# STM32P100.net
KiCad netlist of a schematic drawn in Altium Designer
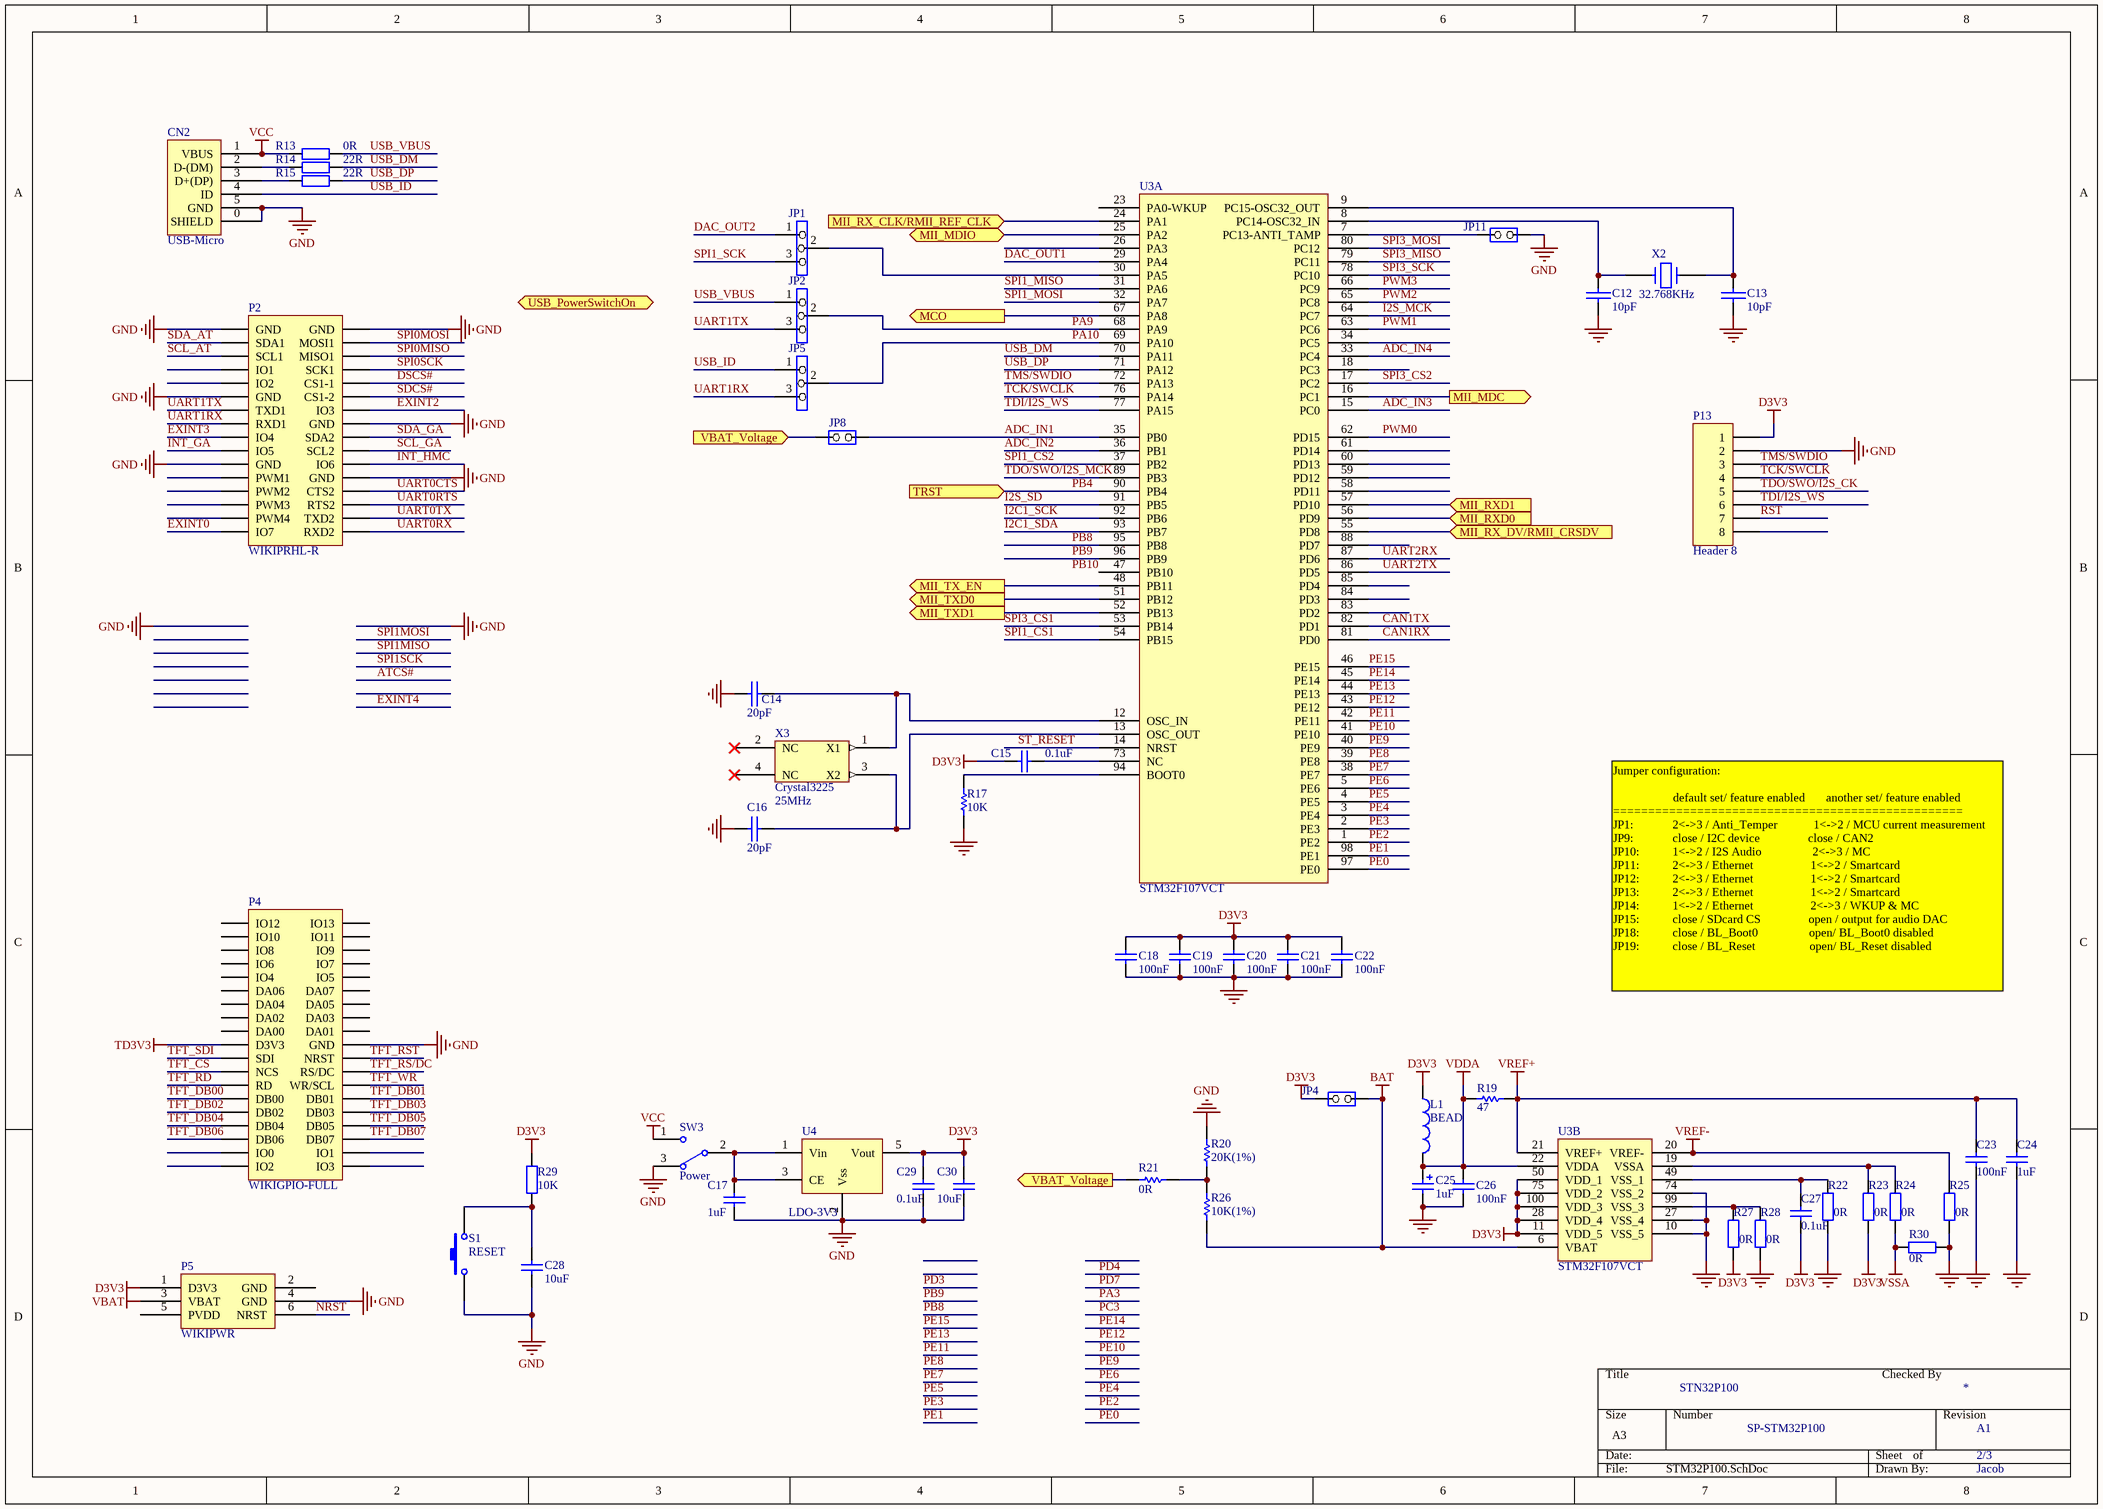
[diagram p0: STM32P100.SchDoc]

(export (version "E")
  (design (tool "Eeschema 10.0.6"))
  (components
    (comp (ref "C12")
      (value "10pF")
      (footprint "0603M")
      (description "Capacitor")
      (libsource (lib "") (part "CAP_1"))
    )
    (comp (ref "C13")
      (value "10pF")
      (footprint "0603M")
      (description "Capacitor")
      (libsource (lib "") (part "CAP_1"))
    )
    (comp (ref "C14")
      (value "20pF")
      (footprint "0603M")
      (description "Capacitor")
      (libsource (lib "*") (part "CAP"))
    )
    (comp (ref "C15")
      (value "0.1uF")
      (footprint "0603M")
      (description "Capacitor")
      (libsource (lib "Studio") (part "Cap"))
    )
    (comp (ref "C16")
      (value "20pF")
      (footprint "0603M")
      (description "Capacitor")
      (libsource (lib "*") (part "CAP"))
    )
    (comp (ref "C17")
      (value "1uF")
      (footprint "0805M")
      (description "Capacitor")
      (fields (field (name "PUBLISHER") "Altium Limited"))
      (libsource (lib "Min's Lib") (part "Cap"))
    )
    (comp (ref "C18")
      (value "100nF")
      (footprint "0603M")
      (description "Capacitor")
      (fields (field (name "PUBLISHER") "Altium Limited"))
      (libsource (lib "Miscellaneous Devices") (part "Cap"))
    )
    (comp (ref "C19")
      (value "100nF")
      (footprint "0603M")
      (description "Capacitor")
      (fields (field (name "PUBLISHER") "Altium Limited"))
      (libsource (lib "Miscellaneous Devices") (part "Cap"))
    )
    (comp (ref "C20")
      (value "100nF")
      (footprint "0603M")
      (description "Capacitor")
      (fields (field (name "PUBLISHER") "Altium Limited"))
      (libsource (lib "Miscellaneous Devices") (part "Cap"))
    )
    (comp (ref "C21")
      (value "100nF")
      (footprint "0603M")
      (description "Capacitor")
      (fields (field (name "PUBLISHER") "Altium Limited"))
      (libsource (lib "Miscellaneous Devices") (part "Cap"))
    )
    (comp (ref "C22")
      (value "100nF")
      (footprint "0603M")
      (description "Capacitor")
      (fields (field (name "PUBLISHER") "Altium Limited"))
      (libsource (lib "Miscellaneous Devices") (part "Cap"))
    )
    (comp (ref "C23")
      (value "100nF")
      (footprint "0603M")
      (description "Capacitor")
      (fields (field (name "PUBLISHER") "Altium Limited"))
      (libsource (lib "Miscellaneous Devices") (part "Cap"))
    )
    (comp (ref "C24")
      (value "1uF")
      (footprint "0603M")
      (description "Capacitor")
      (fields (field (name "PUBLISHER") "Altium Limited"))
      (libsource (lib "Miscellaneous Devices") (part "Cap"))
    )
    (comp (ref "C25")
      (value "1uF")
      (footprint "TAN-A")
      (description "Polarized Capacitor (Radial)")
      (fields (field (name "PUBLISHER") "Altium Limited"))
      (libsource (lib "Miscellaneous Devices") (part "Cap Pol1"))
    )
    (comp (ref "C26")
      (value "100nF")
      (footprint "0603M")
      (description "Capacitor")
      (fields (field (name "PUBLISHER") "Altium Limited"))
      (libsource (lib "Miscellaneous Devices") (part "Cap"))
    )
    (comp (ref "C27")
      (value "0.1uF")
      (footprint "0603M")
      (description "Capacitor")
      (libsource (lib "Studio") (part "Cap"))
    )
    (comp (ref "C28")
      (value "10uF")
      (footprint "0603L")
      (description "Capacitor")
      (fields (field (name "PUBLISHER") "Altium Limited"))
      (libsource (lib "Miscellaneous Devices") (part "Cap"))
    )
    (comp (ref "C29")
      (value "0.1uF")
      (footprint "0603M")
      (description "Capacitor")
      (fields (field (name "PUBLISHER") "Altium Limited"))
      (libsource (lib "Min's Lib") (part "Cap"))
    )
    (comp (ref "C30")
      (value "10uF")
      (footprint "0805M")
      (description "Capacitor")
      (fields (field (name "PUBLISHER") "Altium Limited"))
      (libsource (lib "Min's Lib") (part "Cap"))
    )
    (comp (ref "CN2")
      (value "USB-Micro")
      (footprint "USB-MICRO-Female")
      (libsource (lib "Connector") (part "USB-Micro"))
    )
    (comp (ref "JP1")
      (value "~")
      (footprint "HDR1X3/2.00MM")
      (libsource (lib "STR910_SCHLIB") (part "Jumper3"))
    )
    (comp (ref "JP2")
      (value "~")
      (footprint "HDR1X3/2.00MM")
      (libsource (lib "STR910_SCHLIB") (part "Jumper3"))
    )
    (comp (ref "JP4") (value "~") (footprint "HDR1X2/2.00MM") (libsource (lib "*") (part "JP2")))
    (comp (ref "JP5")
      (value "~")
      (footprint "HDR1X3/2.00MM")
      (libsource (lib "STR910_SCHLIB") (part "Jumper3"))
    )
    (comp (ref "JP8") (value "~") (footprint "HDR1X2/2.00MM") (libsource (lib "*") (part "JP2")))
    (comp (ref "JP11") (value "~") (footprint "HDR1X2/2.00MM") (libsource (lib "*") (part "JP2")))
    (comp (ref "L1")
      (value "BEAD")
      (footprint "0603L")
      (description "Inductor")
      (fields (field (name "PUBLISHER") "Altium Limited"))
      (libsource (lib "Miscellaneous Devices") (part "Inductor"))
    )
    (comp (ref "P2")
      (value "WIKIPRHL-R")
      (footprint "WIKIPRHL-R")
      (description "Header, 16-Pin, Dual row")
      (fields (field (name "PUBLISHER") "Altium Limited"))
      (libsource (lib "Connector") (part "WIKIPRHL-R"))
    )
    (comp (ref "P4")
      (value "WIKIGPIO-FULL")
      (footprint "WIKIGPIO-FULL")
      (description "Header, 19-Pin, Dual row")
      (fields (field (name "PUBLISHER") "Altium Limited"))
      (libsource (lib "Connector") (part "WIKIGPIO-FULL"))
    )
    (comp (ref "P5")
      (value "WIKIPWR")
      (footprint "WIKIPWR")
      (description "PWR HDR")
      (libsource (lib "Connector") (part "WIKIPWR"))
    )
    (comp (ref "P13")
      (value "Header 8")
      (footprint "HDR1X8/2.54MM")
      (description "Header, 8-Pin")
      (fields (field (name "PUBLISHER") "Altium Limited"))
      (libsource (lib "Miscellaneous Connectors") (part "Header 8"))
    )
    (comp (ref "R13")
      (value "0R")
      (footprint "0603M")
      (description "Resistor")
      (fields (field (name "PUBLISHER") "Altium Limited"))
      (libsource (lib "Miscellaneous Devices") (part "Res2"))
    )
    (comp (ref "R14")
      (value "22R")
      (footprint "0603M")
      (description "Resistor")
      (fields (field (name "PUBLISHER") "Altium Limited"))
      (libsource (lib "Miscellaneous Devices") (part "Res2"))
    )
    (comp (ref "R15")
      (value "22R")
      (footprint "0603M")
      (description "Resistor")
      (fields (field (name "PUBLISHER") "Altium Limited"))
      (libsource (lib "Miscellaneous Devices") (part "Res2"))
    )
    (comp (ref "R17")
      (value "10K")
      (footprint "0603M")
      (description "Resistor")
      (fields (field (name "PUBLISHER") "Altium Limited"))
      (libsource (lib "Miscellaneous Devices") (part "res1"))
    )
    (comp (ref "R19")
      (value "47")
      (footprint "0603M")
      (description "Resistor")
      (fields (field (name "PUBLISHER") "Altium Limited"))
      (libsource (lib "Miscellaneous Devices") (part "Res1"))
    )
    (comp (ref "R20")
      (value "20K(1%)")
      (footprint "0603M")
      (description "Resistor")
      (fields (field (name "PUBLISHER") "Altium Limited"))
      (libsource (lib "Miscellaneous Devices") (part "res1"))
    )
    (comp (ref "R21")
      (value "0R")
      (footprint "0603M")
      (description "Resistor")
      (fields (field (name "PUBLISHER") "Altium Limited"))
      (libsource (lib "Miscellaneous Devices") (part "res1"))
    )
    (comp (ref "R22")
      (value "0R")
      (footprint "0603M")
      (description "Resistor")
      (fields (field (name "PUBLISHER") "Altium Limited"))
      (libsource (lib "") (part "Res2_1"))
    )
    (comp (ref "R23")
      (value "0R")
      (footprint "0603M")
      (description "Resistor")
      (fields (field (name "PUBLISHER") "Altium Limited"))
      (libsource (lib "") (part "Res2_1"))
    )
    (comp (ref "R24")
      (value "0R")
      (footprint "0603M")
      (description "Resistor")
      (fields (field (name "PUBLISHER") "Altium Limited"))
      (libsource (lib "") (part "Res2_1"))
    )
    (comp (ref "R25")
      (value "0R")
      (footprint "0603M")
      (description "Resistor")
      (fields (field (name "PUBLISHER") "Altium Limited"))
      (libsource (lib "") (part "Res2_1"))
    )
    (comp (ref "R26")
      (value "10K(1%)")
      (footprint "0603M")
      (description "Resistor")
      (fields (field (name "PUBLISHER") "Altium Limited"))
      (libsource (lib "Miscellaneous Devices") (part "res1"))
    )
    (comp (ref "R27")
      (value "0R")
      (footprint "0603M")
      (description "Resistor")
      (fields (field (name "PUBLISHER") "Altium Limited"))
      (libsource (lib "") (part "Res2_1"))
    )
    (comp (ref "R28")
      (value "0R")
      (footprint "0603M")
      (description "Resistor")
      (fields (field (name "PUBLISHER") "Altium Limited"))
      (libsource (lib "") (part "Res2_1"))
    )
    (comp (ref "R29")
      (value "10K")
      (footprint "0603L")
      (description "Resistor")
      (fields (field (name "PUBLISHER") "Altium Limited"))
      (libsource (lib "") (part "Res2_2"))
    )
    (comp (ref "R30")
      (value "0R")
      (footprint "0603M")
      (description "Resistor")
      (fields (field (name "PUBLISHER") "Altium Limited"))
      (libsource (lib "") (part "Res2_3"))
    )
    (comp (ref "S1")
      (value "RESET")
      (footprint "KEY 6.1*4.0mm")
      (description "Switch")
      (fields (field (name "PUBLISHER") "Altium Limited"))
      (libsource (lib "Miscellaneous Devices") (part "SW-PB"))
    )
    (comp (ref "SW3")
      (value "Power")
      (footprint "HDR1X3/2.54MM")
      (description "SPDT Subminiature Toggle Switch, Right Angle Mounting, Vertical Actuation")
      (fields (field (name "PUBLISHER") "Altium Limited"))
      (libsource (lib "Miscellaneous Devices") (part "SW-SPDT"))
    )
    (comp (ref "U3")
      (value "STM32F107VCT")
      (footprint "LQFP100_N")
      (libsource (lib "MB784") (part "BARRACUDA_256K"))
    )
    (comp (ref "U4")
      (value "LDO-3V3")
      (footprint "SOT23-5")
      (description "LDO")
      (libsource (lib "Min's Lib") (part "XC6219"))
    )
    (comp (ref "X2")
      (value "32.768KHz")
      (footprint "XTAL_32")
      (description "Crystal")
      (libsource (lib "*") (part "CRYSTAL"))
    )
    (comp (ref "X3")
      (value "Crystal3225")
      (footprint "osc3225")
      (fields (field (name "ALTIUM_VALUE") "25MHz"))
      (libsource (lib "Studio") (part "Crystal322"))
    )
  )
  (nets
    (net (code "1") (name "/ADC_IN1") (class "Default")
      (node (ref "JP8") (pin "1") (pinfunction "COMMON_1") (pintype "passive"))
      (node (ref "U3") (pin "35") (pinfunction "PB0_35") (pintype "passive"))
    )
    (net (code "2") (name "/ADC_IN2") (class "Default")
      (node (ref "U3") (pin "36") (pinfunction "PB1_36") (pintype "passive"))
    )
    (net (code "3") (name "/ADC_IN3") (class "Default")
      (node (ref "U3") (pin "15") (pinfunction "PC0_15") (pintype "passive"))
    )
    (net (code "4") (name "/ADC_IN4") (class "Default")
      (node (ref "U3") (pin "33") (pinfunction "PC4_33") (pintype "passive"))
    )
    (net (code "6") (name "/CAN1RX") (class "Default")
      (node (ref "U3") (pin "81") (pinfunction "PD0_81") (pintype "passive"))
    )
    (net (code "7") (name "/CAN1TX") (class "Default")
      (node (ref "U3") (pin "82") (pinfunction "PD1_82") (pintype "passive"))
    )
    (net (code "8") (name "/DAC_OUT1") (class "Default")
      (node (ref "U3") (pin "29") (pinfunction "PA4_29") (pintype "passive"))
    )
    (net (code "9") (name "/DAC_OUT2") (class "Default") (node (ref "JP1") (pin "1") (pintype "passive")))
    (net (code "10") (name "/DSCS#") (class "Default")
      (node (ref "P2") (pin "10") (pinfunction "CS1-1_10") (pintype "passive"))
    )
    (net (code "11") (name "/EXINT0") (class "Default")
      (node (ref "P2") (pin "31") (pinfunction "IO7_31") (pintype "passive"))
    )
    (net (code "12") (name "/EXINT2") (class "Default")
      (node (ref "P2") (pin "14") (pinfunction "IO3_14") (pintype "passive"))
    )
    (net (code "13") (name "/EXINT3") (class "Default")
      (node (ref "P2") (pin "17") (pinfunction "IO4_17") (pintype "passive"))
    )
    (net (code "15") (name "/I2C1_SCK") (class "Default")
      (node (ref "U3") (pin "92") (pinfunction "PB6_92") (pintype "passive"))
    )
    (net (code "16") (name "/I2C1_SDA") (class "Default")
      (node (ref "U3") (pin "93") (pinfunction "PB7_93") (pintype "passive"))
    )
    (net (code "17") (name "/I2S_MCK") (class "Default")
      (node (ref "U3") (pin "64") (pinfunction "PC7_64") (pintype "passive"))
    )
    (net (code "18") (name "/I2S_SD") (class "Default")
      (node (ref "U3") (pin "91") (pinfunction "PB5_91") (pintype "passive"))
    )
    (net (code "19") (name "/INT_GA") (class "Default")
      (node (ref "P2") (pin "19") (pinfunction "IO5_19") (pintype "passive"))
    )
    (net (code "20") (name "/INT_HMC") (class "Default")
      (node (ref "P2") (pin "22") (pinfunction "IO6_22") (pintype "passive"))
    )
    (net (code "21") (name "/MCO") (class "Default")
      (node (ref "U3") (pin "67") (pinfunction "PA8_67") (pintype "passive"))
    )
    (net (code "22") (name "/MII_MDC") (class "Default")
      (node (ref "U3") (pin "16") (pinfunction "PC1_16") (pintype "passive"))
    )
    (net (code "23") (name "/MII_MDIO") (class "Default")
      (node (ref "U3") (pin "25") (pinfunction "PA2_25") (pintype "passive"))
    )
    (net (code "24") (name "/MII_RXD0") (class "Default")
      (node (ref "U3") (pin "56") (pinfunction "PD9_56") (pintype "passive"))
    )
    (net (code "25") (name "/MII_RXD1") (class "Default")
      (node (ref "U3") (pin "57") (pinfunction "PD10_57") (pintype "passive"))
    )
    (net (code "26") (name "/MII_RX_CLK{slash}RMII_REF_CLK") (class "Default")
      (node (ref "U3") (pin "24") (pinfunction "PA1_24") (pintype "passive"))
    )
    (net (code "27") (name "/MII_RX_DV{slash}RMII_CRSDV") (class "Default")
      (node (ref "U3") (pin "55") (pinfunction "PD8_55") (pintype "passive"))
    )
    (net (code "28") (name "/MII_TXD0") (class "Default")
      (node (ref "U3") (pin "51") (pinfunction "PB12_51") (pintype "passive"))
    )
    (net (code "29") (name "/MII_TXD1") (class "Default")
      (node (ref "U3") (pin "52") (pinfunction "PB13_52") (pintype "passive"))
    )
    (net (code "30") (name "/MII_TX_EN") (class "Default")
      (node (ref "U3") (pin "48") (pinfunction "PB11_48") (pintype "passive"))
    )
    (net (code "31") (name "/NRST") (class "Default")
      (node (ref "P5") (pin "6") (pinfunction "NRST_6") (pintype "passive"))
    )
    (net (code "33") (name "/PA9") (class "Default")
      (node (ref "JP2") (pin "2") (pintype "passive"))
      (node (ref "U3") (pin "68") (pinfunction "PA9_68") (pintype "passive"))
    )
    (net (code "34") (name "/PA10") (class "Default")
      (node (ref "JP5") (pin "2") (pintype "passive"))
      (node (ref "U3") (pin "69") (pinfunction "PA10_69") (pintype "passive"))
    )
    (net (code "35") (name "/PB4") (class "Default")
      (node (ref "U3") (pin "90") (pinfunction "PB4_90") (pintype "passive"))
    )
    (net (code "36") (name "/PB8") (class "Default")
      (node (ref "U3") (pin "95") (pinfunction "PB8_95") (pintype "passive"))
    )
    (net (code "37") (name "/PB9") (class "Default")
      (node (ref "U3") (pin "96") (pinfunction "PB9_96") (pintype "passive"))
    )
    (net (code "43") (name "/PE0") (class "Default")
      (node (ref "U3") (pin "97") (pinfunction "PE0_97") (pintype "passive"))
    )
    (net (code "44") (name "/PE1") (class "Default")
      (node (ref "U3") (pin "98") (pinfunction "PE1_98") (pintype "passive"))
    )
    (net (code "45") (name "/PE2") (class "Default")
      (node (ref "U3") (pin "1") (pinfunction "PE2_1") (pintype "passive"))
    )
    (net (code "46") (name "/PE3") (class "Default")
      (node (ref "U3") (pin "2") (pinfunction "PE3_2") (pintype "passive"))
    )
    (net (code "47") (name "/PE4") (class "Default")
      (node (ref "U3") (pin "3") (pinfunction "PE4_3") (pintype "passive"))
    )
    (net (code "48") (name "/PE5") (class "Default")
      (node (ref "U3") (pin "4") (pinfunction "PE5_4") (pintype "passive"))
    )
    (net (code "49") (name "/PE6") (class "Default")
      (node (ref "U3") (pin "5") (pinfunction "PE6_5") (pintype "passive"))
    )
    (net (code "50") (name "/PE7") (class "Default")
      (node (ref "U3") (pin "38") (pinfunction "PE7_38") (pintype "passive"))
    )
    (net (code "51") (name "/PE8") (class "Default")
      (node (ref "U3") (pin "39") (pinfunction "PE8_39") (pintype "passive"))
    )
    (net (code "52") (name "/PE9") (class "Default")
      (node (ref "U3") (pin "40") (pinfunction "PE9_40") (pintype "passive"))
    )
    (net (code "53") (name "/PE10") (class "Default")
      (node (ref "U3") (pin "41") (pinfunction "PE10_41") (pintype "passive"))
    )
    (net (code "54") (name "/PE11") (class "Default")
      (node (ref "U3") (pin "42") (pinfunction "PE11_42") (pintype "passive"))
    )
    (net (code "55") (name "/PE12") (class "Default")
      (node (ref "U3") (pin "43") (pinfunction "PE12_43") (pintype "passive"))
    )
    (net (code "56") (name "/PE13") (class "Default")
      (node (ref "U3") (pin "44") (pinfunction "PE13_44") (pintype "passive"))
    )
    (net (code "57") (name "/PE14") (class "Default")
      (node (ref "U3") (pin "45") (pinfunction "PE14_45") (pintype "passive"))
    )
    (net (code "58") (name "/PE15") (class "Default")
      (node (ref "U3") (pin "46") (pinfunction "PE15_46") (pintype "passive"))
    )
    (net (code "59") (name "/PWM0") (class "Default")
      (node (ref "U3") (pin "62") (pinfunction "PD15_62") (pintype "passive"))
    )
    (net (code "60") (name "/PWM1") (class "Default")
      (node (ref "U3") (pin "63") (pinfunction "PC6_63") (pintype "passive"))
    )
    (net (code "61") (name "/PWM2") (class "Default")
      (node (ref "U3") (pin "65") (pinfunction "PC8_65") (pintype "passive"))
    )
    (net (code "62") (name "/PWM3") (class "Default")
      (node (ref "U3") (pin "66") (pinfunction "PC9_66") (pintype "passive"))
    )
    (net (code "63") (name "/RST") (class "Default")
      (node (ref "P13") (pin "7") (pinfunction "7_7") (pintype "passive"))
    )
    (net (code "64") (name "/SCL_AT") (class "Default")
      (node (ref "P2") (pin "5") (pinfunction "SCL1_5") (pintype "passive"))
    )
    (net (code "65") (name "/SCL_GA") (class "Default")
      (node (ref "P2") (pin "20") (pinfunction "SCL2_20") (pintype "passive"))
    )
    (net (code "66") (name "/SDA_AT") (class "Default")
      (node (ref "P2") (pin "3") (pinfunction "SDA1_3") (pintype "passive"))
    )
    (net (code "67") (name "/SDA_GA") (class "Default")
      (node (ref "P2") (pin "18") (pinfunction "SDA2_18") (pintype "passive"))
    )
    (net (code "68") (name "/SDCS#") (class "Default")
      (node (ref "P2") (pin "12") (pinfunction "CS1-2_12") (pintype "passive"))
    )
    (net (code "69") (name "/SPI0MISO") (class "Default")
      (node (ref "P2") (pin "6") (pinfunction "MISO1_6") (pintype "passive"))
    )
    (net (code "70") (name "/SPI0MOSI") (class "Default")
      (node (ref "P2") (pin "4") (pinfunction "MOSI1_4") (pintype "passive"))
    )
    (net (code "71") (name "/SPI0SCK") (class "Default")
      (node (ref "P2") (pin "8") (pinfunction "SCK1_8") (pintype "passive"))
    )
    (net (code "75") (name "/SPI1_CS1") (class "Default")
      (node (ref "U3") (pin "54") (pinfunction "PB15_54") (pintype "passive"))
    )
    (net (code "76") (name "/SPI1_CS2") (class "Default")
      (node (ref "U3") (pin "37") (pinfunction "PB2_37") (pintype "passive"))
    )
    (net (code "77") (name "/SPI1_MISO") (class "Default")
      (node (ref "U3") (pin "31") (pinfunction "PA6_31") (pintype "passive"))
    )
    (net (code "78") (name "/SPI1_MOSI") (class "Default")
      (node (ref "U3") (pin "32") (pinfunction "PA7_32") (pintype "passive"))
    )
    (net (code "79") (name "/SPI1_SCK") (class "Default") (node (ref "JP1") (pin "3") (pintype "passive")))
    (net (code "80") (name "/SPI3_CS1") (class "Default")
      (node (ref "U3") (pin "53") (pinfunction "PB14_53") (pintype "passive"))
    )
    (net (code "81") (name "/SPI3_CS2") (class "Default")
      (node (ref "U3") (pin "17") (pinfunction "PC2_17") (pintype "passive"))
    )
    (net (code "82") (name "/SPI3_MISO") (class "Default")
      (node (ref "U3") (pin "79") (pinfunction "PC11_79") (pintype "passive"))
    )
    (net (code "83") (name "/SPI3_MOSI") (class "Default")
      (node (ref "U3") (pin "80") (pinfunction "PC12_80") (pintype "passive"))
    )
    (net (code "84") (name "/SPI3_SCK") (class "Default")
      (node (ref "U3") (pin "78") (pinfunction "PC10_78") (pintype "passive"))
    )
    (net (code "85") (name "/ST_RESET") (class "Default")
      (node (ref "U3") (pin "14") (pinfunction "NRST_14") (pintype "passive"))
    )
    (net (code "86") (name "/TCK{slash}SWCLK") (class "Default")
      (node (ref "P13") (pin "4") (pinfunction "4_4") (pintype "passive"))
      (node (ref "U3") (pin "76") (pinfunction "PA14_76") (pintype "passive"))
    )
    (net (code "87") (name "/TDI{slash}I2S_WS") (class "Default")
      (node (ref "P13") (pin "6") (pinfunction "6_6") (pintype "passive"))
      (node (ref "U3") (pin "77") (pinfunction "PA15_77") (pintype "passive"))
    )
    (net (code "88") (name "/TDO{slash}SWO{slash}I2S_CK") (class "Default")
      (node (ref "P13") (pin "5") (pinfunction "5_5") (pintype "passive"))
    )
    (net (code "89") (name "/TDO{slash}SWO{slash}I2S_MCK") (class "Default")
      (node (ref "U3") (pin "89") (pinfunction "PB3_89") (pintype "passive"))
    )
    (net (code "90") (name "/TFT_CS") (class "Default")
      (node (ref "P4") (pin "23") (pinfunction "NCS_23") (pintype "passive"))
    )
    (net (code "91") (name "/TFT_DB00") (class "Default")
      (node (ref "P4") (pin "27") (pinfunction "DB00_27") (pintype "passive"))
    )
    (net (code "92") (name "/TFT_DB01") (class "Default")
      (node (ref "P4") (pin "28") (pinfunction "DB01_28") (pintype "passive"))
    )
    (net (code "93") (name "/TFT_DB02") (class "Default")
      (node (ref "P4") (pin "29") (pinfunction "DB02_29") (pintype "passive"))
    )
    (net (code "94") (name "/TFT_DB03") (class "Default")
      (node (ref "P4") (pin "30") (pinfunction "DB03_30") (pintype "passive"))
    )
    (net (code "95") (name "/TFT_DB04") (class "Default")
      (node (ref "P4") (pin "31") (pinfunction "DB04_31") (pintype "passive"))
    )
    (net (code "96") (name "/TFT_DB05") (class "Default")
      (node (ref "P4") (pin "32") (pinfunction "DB05_32") (pintype "passive"))
    )
    (net (code "97") (name "/TFT_DB06") (class "Default")
      (node (ref "P4") (pin "33") (pinfunction "DB06_33") (pintype "passive"))
    )
    (net (code "98") (name "/TFT_DB07") (class "Default")
      (node (ref "P4") (pin "34") (pinfunction "DB07_34") (pintype "passive"))
    )
    (net (code "99") (name "/TFT_RD") (class "Default")
      (node (ref "P4") (pin "25") (pinfunction "RD_25") (pintype "passive"))
    )
    (net (code "100") (name "/TFT_RST") (class "Default")
      (node (ref "P4") (pin "22") (pinfunction "NRST_22") (pintype "passive"))
    )
    (net (code "101") (name "/TFT_RS{slash}DC") (class "Default")
      (node (ref "P4") (pin "24") (pinfunction "RS/DC_24") (pintype "passive"))
    )
    (net (code "102") (name "/TFT_SDI") (class "Default")
      (node (ref "P4") (pin "21") (pinfunction "SDI_21") (pintype "passive"))
    )
    (net (code "103") (name "/TFT_WR") (class "Default")
      (node (ref "P4") (pin "26") (pinfunction "WR/SCL_26") (pintype "passive"))
    )
    (net (code "104") (name "/TMS{slash}SWDIO") (class "Default")
      (node (ref "P13") (pin "3") (pinfunction "3_3") (pintype "passive"))
      (node (ref "U3") (pin "72") (pinfunction "PA13_72") (pintype "passive"))
    )
    (net (code "105") (name "/UART0CTS") (class "Default")
      (node (ref "P2") (pin "26") (pinfunction "CTS2_26") (pintype "passive"))
    )
    (net (code "106") (name "/UART0RTS") (class "Default")
      (node (ref "P2") (pin "28") (pinfunction "RTS2_28") (pintype "passive"))
    )
    (net (code "107") (name "/UART0RX") (class "Default")
      (node (ref "P2") (pin "32") (pinfunction "RXD2_32") (pintype "passive"))
    )
    (net (code "108") (name "/UART0TX") (class "Default")
      (node (ref "P2") (pin "30") (pinfunction "TXD2_30") (pintype "passive"))
    )
    (net (code "109") (name "/UART1RX") (class "Default")
      (node (ref "JP5") (pin "3") (pintype "passive"))
      (node (ref "P2") (pin "15") (pinfunction "RXD1_15") (pintype "passive"))
    )
    (net (code "110") (name "/UART1TX") (class "Default")
      (node (ref "JP2") (pin "3") (pintype "passive"))
      (node (ref "P2") (pin "13") (pinfunction "TXD1_13") (pintype "passive"))
    )
    (net (code "111") (name "/UART2RX") (class "Default")
      (node (ref "U3") (pin "87") (pinfunction "PD6_87") (pintype "passive"))
    )
    (net (code "112") (name "/UART2TX") (class "Default")
      (node (ref "U3") (pin "86") (pinfunction "PD5_86") (pintype "passive"))
    )
    (net (code "113") (name "/USB_DM") (class "Default")
      (node (ref "R14") (pin "2") (pinfunction "2_2") (pintype "passive"))
      (node (ref "U3") (pin "70") (pinfunction "PA11_70") (pintype "passive"))
    )
    (net (code "114") (name "/USB_DP") (class "Default")
      (node (ref "R15") (pin "2") (pinfunction "2_2") (pintype "passive"))
      (node (ref "U3") (pin "71") (pinfunction "PA12_71") (pintype "passive"))
    )
    (net (code "115") (name "/USB_ID") (class "Default")
      (node (ref "CN2") (pin "4") (pinfunction "ID_4") (pintype "passive"))
      (node (ref "JP5") (pin "1") (pintype "passive"))
    )
    (net (code "117") (name "/USB_VBUS") (class "Default")
      (node (ref "JP2") (pin "1") (pintype "passive"))
      (node (ref "R13") (pin "2") (pinfunction "2_2") (pintype "passive"))
    )
    (net (code "118") (name "/VBAT_Voltage") (class "Default")
      (node (ref "JP8") (pin "2") (pinfunction "NO_2") (pintype "passive"))
      (node (ref "R21") (pin "1") (pinfunction "1_1") (pintype "passive"))
    )
    (net (code "119") (name "BAT") (class "Default")
      (node (ref "JP4") (pin "1") (pinfunction "COMMON_1") (pintype "passive"))
      (node (ref "R26") (pin "2") (pinfunction "2_2") (pintype "passive"))
      (node (ref "U3") (pin "6") (pinfunction "VBAT_6") (pintype "passive"))
    )
    (net (code "120") (name "D3V3") (class "Default")
      (node (ref "C15") (pin "1") (pinfunction "1_1") (pintype "passive"))
      (node (ref "C18") (pin "1") (pinfunction "1_1") (pintype "passive"))
      (node (ref "C19") (pin "1") (pinfunction "1_1") (pintype "passive"))
      (node (ref "C20") (pin "1") (pinfunction "1_1") (pintype "passive"))
      (node (ref "C21") (pin "1") (pinfunction "1_1") (pintype "passive"))
      (node (ref "C22") (pin "1") (pinfunction "1_1") (pintype "passive"))
      (node (ref "C27") (pin "1") (pinfunction "1_1") (pintype "passive"))
      (node (ref "C29") (pin "1") (pinfunction "1_1") (pintype "passive"))
      (node (ref "C30") (pin "1") (pinfunction "1_1") (pintype "passive"))
      (node (ref "JP4") (pin "2") (pinfunction "NO_2") (pintype "passive"))
      (node (ref "L1") (pin "1") (pinfunction "1_1") (pintype "passive"))
      (node (ref "P13") (pin "1") (pinfunction "1_1") (pintype "passive"))
      (node (ref "P5") (pin "1") (pinfunction "D3V3_1") (pintype "passive"))
      (node (ref "R23") (pin "2") (pinfunction "2_2") (pintype "passive"))
      (node (ref "R27") (pin "2") (pinfunction "2_2") (pintype "passive"))
      (node (ref "R29") (pin "2") (pinfunction "2_2") (pintype "passive"))
      (node (ref "U3") (pin "100") (pinfunction "VDD_3_100") (pintype "passive"))
      (node (ref "U3") (pin "11") (pinfunction "VDD_5_11") (pintype "passive"))
      (node (ref "U3") (pin "28") (pinfunction "VDD_4_28") (pintype "passive"))
      (node (ref "U3") (pin "50") (pinfunction "VDD_1_50") (pintype "passive"))
      (node (ref "U3") (pin "75") (pinfunction "VDD_2_75") (pintype "passive"))
      (node (ref "U4") (pin "5") (pinfunction "Vout_5") (pintype "passive"))
    )
    (net (code "121") (name "GND") (class "Default")
      (node (ref "C12") (pin "2") (pinfunction "2_2") (pintype "passive"))
      (node (ref "C13") (pin "2") (pinfunction "2_2") (pintype "passive"))
      (node (ref "C14") (pin "2") (pinfunction "2_2") (pintype "passive"))
      (node (ref "C16") (pin "2") (pinfunction "2_2") (pintype "passive"))
      (node (ref "C17") (pin "2") (pinfunction "2_2") (pintype "passive"))
      (node (ref "C18") (pin "2") (pinfunction "2_2") (pintype "passive"))
      (node (ref "C19") (pin "2") (pinfunction "2_2") (pintype "passive"))
      (node (ref "C20") (pin "2") (pinfunction "2_2") (pintype "passive"))
      (node (ref "C21") (pin "2") (pinfunction "2_2") (pintype "passive"))
      (node (ref "C22") (pin "2") (pinfunction "2_2") (pintype "passive"))
      (node (ref "C23") (pin "2") (pinfunction "2_2") (pintype "passive"))
      (node (ref "C24") (pin "2") (pinfunction "2_2") (pintype "passive"))
      (node (ref "C25") (pin "2") (pinfunction "2_2") (pintype "passive"))
      (node (ref "C26") (pin "2") (pinfunction "2_2") (pintype "passive"))
      (node (ref "C28") (pin "1") (pinfunction "1_1") (pintype "passive"))
      (node (ref "C29") (pin "2") (pinfunction "2_2") (pintype "passive"))
      (node (ref "C30") (pin "2") (pinfunction "2_2") (pintype "passive"))
      (node (ref "CN2") (pin "0") (pinfunction "SHIELD_0") (pintype "passive"))
      (node (ref "CN2") (pin "5") (pinfunction "GND_5") (pintype "passive"))
      (node (ref "JP11") (pin "1") (pinfunction "COMMON_1") (pintype "passive"))
      (node (ref "P13") (pin "2") (pinfunction "2_2") (pintype "passive"))
      (node (ref "P2") (pin "1") (pinfunction "GND_1") (pintype "passive"))
      (node (ref "P2") (pin "11") (pinfunction "GND_11") (pintype "passive"))
      (node (ref "P2") (pin "16") (pinfunction "GND_16") (pintype "passive"))
      (node (ref "P2") (pin "2") (pinfunction "GND_2") (pintype "passive"))
      (node (ref "P2") (pin "21") (pinfunction "GND_21") (pintype "passive"))
      (node (ref "P2") (pin "24") (pinfunction "GND_24") (pintype "passive"))
      (node (ref "P4") (pin "20") (pinfunction "GND_20") (pintype "passive"))
      (node (ref "P5") (pin "4") (pinfunction "GND_4") (pintype "passive"))
      (node (ref "R17") (pin "2") (pinfunction "2_2") (pintype "passive"))
      (node (ref "R20") (pin "1") (pinfunction "1_1") (pintype "passive"))
      (node (ref "R22") (pin "2") (pinfunction "2_2") (pintype "passive"))
      (node (ref "R25") (pin "2") (pinfunction "2_2") (pintype "passive"))
      (node (ref "R28") (pin "2") (pinfunction "2_2") (pintype "passive"))
      (node (ref "R30") (pin "1") (pinfunction "1_1") (pintype "passive"))
      (node (ref "S1") (pin "1") (pinfunction "1_1") (pintype "passive"))
      (node (ref "SW3") (pin "3") (pintype "passive"))
      (node (ref "U3") (pin "10") (pinfunction "VSS_5_10") (pintype "passive"))
      (node (ref "U3") (pin "27") (pinfunction "VSS_4_27") (pintype "passive"))
      (node (ref "U3") (pin "74") (pinfunction "VSS_2_74") (pintype "passive"))
      (node (ref "U4") (pin "2") (pinfunction "Vss_2") (pintype "passive"))
    )
    (net (code "122") (name "Net-(C28-Pad2)") (class "Default")
      (node (ref "C28") (pin "2") (pinfunction "2_2") (pintype "passive"))
      (node (ref "R29") (pin "1") (pinfunction "1_1") (pintype "passive"))
      (node (ref "S1") (pin "2") (pinfunction "2_2") (pintype "passive"))
    )
    (net (code "123") (name "Net-(CN2-D+(DP))") (class "Default")
      (node (ref "CN2") (pin "3") (pinfunction "D+(DP)_3") (pintype "passive"))
      (node (ref "R15") (pin "1") (pinfunction "1_1") (pintype "passive"))
    )
    (net (code "124") (name "Net-(CN2-D-(DM))") (class "Default")
      (node (ref "CN2") (pin "2") (pinfunction "D-(DM)_2") (pintype "passive"))
      (node (ref "R14") (pin "1") (pinfunction "1_1") (pintype "passive"))
    )
    (net (code "125") (name "Net-(JP11-NO)") (class "Default")
      (node (ref "JP11") (pin "2") (pinfunction "NO_2") (pintype "passive"))
      (node (ref "U3") (pin "7") (pinfunction "PC13-ANTI_TAMP_7") (pintype "passive"))
    )
    (net (code "126") (name "Net-(R20-Pad2)") (class "Default")
      (node (ref "R20") (pin "2") (pinfunction "2_2") (pintype "passive"))
      (node (ref "R21") (pin "2") (pinfunction "2_2") (pintype "passive"))
      (node (ref "R26") (pin "1") (pinfunction "1_1") (pintype "passive"))
    )
    (net (code "127") (name "Net-(U3A-BOOT0)") (class "Default")
      (node (ref "R17") (pin "1") (pinfunction "1_1") (pintype "passive"))
      (node (ref "U3") (pin "94") (pinfunction "BOOT0_94") (pintype "passive"))
    )
    (net (code "128") (name "Net-(U3A-NC)") (class "Default")
      (node (ref "C15") (pin "2") (pinfunction "2_2") (pintype "passive"))
      (node (ref "U3") (pin "73") (pinfunction "NC_73") (pintype "passive"))
    )
    (net (code "129") (name "Net-(U3A-OSC_IN)") (class "Default")
      (node (ref "C14") (pin "1") (pinfunction "1_1") (pintype "passive"))
      (node (ref "U3") (pin "12") (pinfunction "OSC_IN_12") (pintype "passive"))
      (node (ref "X3") (pin "1") (pinfunction "X1_1") (pintype "output"))
    )
    (net (code "130") (name "Net-(U3A-OSC_OUT)") (class "Default")
      (node (ref "C16") (pin "1") (pinfunction "1_1") (pintype "passive"))
      (node (ref "U3") (pin "13") (pinfunction "OSC_OUT_13") (pintype "passive"))
      (node (ref "X3") (pin "3") (pinfunction "X2_3") (pintype "output"))
    )
    (net (code "131") (name "Net-(U3A-PA5)") (class "Default")
      (node (ref "JP1") (pin "2") (pintype "passive"))
      (node (ref "U3") (pin "30") (pinfunction "PA5_30") (pintype "passive"))
    )
    (net (code "132") (name "Net-(U3A-PC14-OSC32_IN)") (class "Default")
      (node (ref "C12") (pin "1") (pinfunction "1_1") (pintype "passive"))
      (node (ref "U3") (pin "8") (pinfunction "PC14-OSC32_IN_8") (pintype "passive"))
      (node (ref "X2") (pin "2") (pinfunction "2_2") (pintype "passive"))
    )
    (net (code "133") (name "Net-(U3A-PC15-OSC32_OUT)") (class "Default")
      (node (ref "C13") (pin "1") (pinfunction "1_1") (pintype "passive"))
      (node (ref "U3") (pin "9") (pinfunction "PC15-OSC32_OUT_9") (pintype "passive"))
      (node (ref "X2") (pin "1") (pinfunction "1_1") (pintype "passive"))
    )
    (net (code "134") (name "Net-(U3B-VSSA)") (class "Default")
      (node (ref "R23") (pin "1") (pinfunction "1_1") (pintype "passive"))
      (node (ref "R24") (pin "1") (pinfunction "1_1") (pintype "passive"))
      (node (ref "U3") (pin "19") (pinfunction "VSSA_19") (pintype "passive"))
    )
    (net (code "135") (name "Net-(U3B-VSS_1)") (class "Default")
      (node (ref "C27") (pin "2") (pinfunction "2_2") (pintype "passive"))
      (node (ref "R22") (pin "1") (pinfunction "1_1") (pintype "passive"))
      (node (ref "U3") (pin "49") (pinfunction "VSS_1_49") (pintype "passive"))
    )
    (net (code "136") (name "Net-(U3B-VSS_3)") (class "Default")
      (node (ref "R27") (pin "1") (pinfunction "1_1") (pintype "passive"))
      (node (ref "R28") (pin "1") (pinfunction "1_1") (pintype "passive"))
      (node (ref "U3") (pin "99") (pinfunction "VSS_3_99") (pintype "passive"))
    )
    (net (code "137") (name "Net-(U4-CE)") (class "Default")
      (node (ref "C17") (pin "1") (pinfunction "1_1") (pintype "passive"))
      (node (ref "SW3") (pin "2") (pintype "passive"))
      (node (ref "U4") (pin "1") (pinfunction "Vin_1") (pintype "passive"))
      (node (ref "U4") (pin "3") (pinfunction "CE_3") (pintype "passive"))
    )
    (net (code "138") (name "TD3V3") (class "Default")
      (node (ref "P4") (pin "19") (pinfunction "D3V3_19") (pintype "passive"))
    )
    (net (code "139") (name "VBAT") (class "Default")
      (node (ref "P5") (pin "3") (pinfunction "VBAT_3") (pintype "passive"))
    )
    (net (code "140") (name "VCC") (class "Default")
      (node (ref "CN2") (pin "1") (pinfunction "VBUS_1") (pintype "passive"))
      (node (ref "R13") (pin "1") (pinfunction "1_1") (pintype "passive"))
      (node (ref "SW3") (pin "1") (pintype "passive"))
    )
    (net (code "141") (name "VDDA") (class "Default")
      (node (ref "C25") (pin "1") (pinfunction "1_1") (pintype "passive"))
      (node (ref "C26") (pin "1") (pinfunction "1_1") (pintype "passive"))
      (node (ref "L1") (pin "2") (pinfunction "2_2") (pintype "passive"))
      (node (ref "R19") (pin "2") (pinfunction "2_2") (pintype "passive"))
      (node (ref "U3") (pin "22") (pinfunction "VDDA_22") (pintype "passive"))
    )
    (net (code "142") (name "VREF+") (class "Default")
      (node (ref "C23") (pin "1") (pinfunction "1_1") (pintype "passive"))
      (node (ref "C24") (pin "1") (pinfunction "1_1") (pintype "passive"))
      (node (ref "R19") (pin "1") (pinfunction "1_1") (pintype "passive"))
      (node (ref "U3") (pin "21") (pinfunction "VREF+_21") (pintype "passive"))
    )
    (net (code "143") (name "VREF-") (class "Default")
      (node (ref "R25") (pin "1") (pinfunction "1_1") (pintype "passive"))
      (node (ref "U3") (pin "20") (pinfunction "VREF-_20") (pintype "passive"))
    )
    (net (code "144") (name "VSSA") (class "Default")
      (node (ref "R24") (pin "2") (pinfunction "2_2") (pintype "passive"))
      (node (ref "R30") (pin "2") (pinfunction "2_2") (pintype "passive"))
    )
    (net (code "145") (name "unconnected-(P2-IO1-Pad7)") (class "Default")
      (node (ref "P2") (pin "7") (pinfunction "IO1_7") (pintype "passive"))
    )
    (net (code "146") (name "unconnected-(P2-IO2-Pad9)") (class "Default")
      (node (ref "P2") (pin "9") (pinfunction "IO2_9") (pintype "passive"))
    )
    (net (code "147") (name "unconnected-(P2-PWM1-Pad23)") (class "Default")
      (node (ref "P2") (pin "23") (pinfunction "PWM1_23") (pintype "passive"))
    )
    (net (code "148") (name "unconnected-(P2-PWM2-Pad25)") (class "Default")
      (node (ref "P2") (pin "25") (pinfunction "PWM2_25") (pintype "passive"))
    )
    (net (code "149") (name "unconnected-(P2-PWM3-Pad27)") (class "Default")
      (node (ref "P2") (pin "27") (pinfunction "PWM3_27") (pintype "passive"))
    )
    (net (code "150") (name "unconnected-(P2-PWM4-Pad29)") (class "Default")
      (node (ref "P2") (pin "29") (pinfunction "PWM4_29") (pintype "passive"))
    )
    (net (code "151") (name "unconnected-(P4-DA00-Pad17)") (class "Default")
      (node (ref "P4") (pin "17") (pinfunction "DA00_17") (pintype "passive"))
    )
    (net (code "152") (name "unconnected-(P4-DA01-Pad18)") (class "Default")
      (node (ref "P4") (pin "18") (pinfunction "DA01_18") (pintype "passive"))
    )
    (net (code "153") (name "unconnected-(P4-DA02-Pad15)") (class "Default")
      (node (ref "P4") (pin "15") (pinfunction "DA02_15") (pintype "passive"))
    )
    (net (code "154") (name "unconnected-(P4-DA03-Pad16)") (class "Default")
      (node (ref "P4") (pin "16") (pinfunction "DA03_16") (pintype "passive"))
    )
    (net (code "155") (name "unconnected-(P4-DA04-Pad13)") (class "Default")
      (node (ref "P4") (pin "13") (pinfunction "DA04_13") (pintype "passive"))
    )
    (net (code "156") (name "unconnected-(P4-DA05-Pad14)") (class "Default")
      (node (ref "P4") (pin "14") (pinfunction "DA05_14") (pintype "passive"))
    )
    (net (code "157") (name "unconnected-(P4-DA06-Pad11)") (class "Default")
      (node (ref "P4") (pin "11") (pinfunction "DA06_11") (pintype "passive"))
    )
    (net (code "158") (name "unconnected-(P4-DA07-Pad12)") (class "Default")
      (node (ref "P4") (pin "12") (pinfunction "DA07_12") (pintype "passive"))
    )
    (net (code "159") (name "unconnected-(P4-IO0-Pad35)") (class "Default")
      (node (ref "P4") (pin "35") (pinfunction "IO0_35") (pintype "passive"))
    )
    (net (code "160") (name "unconnected-(P4-IO1-Pad36)") (class "Default")
      (node (ref "P4") (pin "36") (pinfunction "IO1_36") (pintype "passive"))
    )
    (net (code "161") (name "unconnected-(P4-IO2-Pad37)") (class "Default")
      (node (ref "P4") (pin "37") (pinfunction "IO2_37") (pintype "passive"))
    )
    (net (code "162") (name "unconnected-(P4-IO3-Pad38)") (class "Default")
      (node (ref "P4") (pin "38") (pinfunction "IO3_38") (pintype "passive"))
    )
    (net (code "163") (name "unconnected-(P4-IO4-Pad9)") (class "Default")
      (node (ref "P4") (pin "9") (pinfunction "IO4_9") (pintype "passive"))
    )
    (net (code "164") (name "unconnected-(P4-IO5-Pad10)") (class "Default")
      (node (ref "P4") (pin "10") (pinfunction "IO5_10") (pintype "passive"))
    )
    (net (code "165") (name "unconnected-(P4-IO6-Pad7)") (class "Default")
      (node (ref "P4") (pin "7") (pinfunction "IO6_7") (pintype "passive"))
    )
    (net (code "166") (name "unconnected-(P4-IO7-Pad8)") (class "Default")
      (node (ref "P4") (pin "8") (pinfunction "IO7_8") (pintype "passive"))
    )
    (net (code "167") (name "unconnected-(P4-IO8-Pad5)") (class "Default")
      (node (ref "P4") (pin "5") (pinfunction "IO8_5") (pintype "passive"))
    )
    (net (code "168") (name "unconnected-(P4-IO9-Pad6)") (class "Default")
      (node (ref "P4") (pin "6") (pinfunction "IO9_6") (pintype "passive"))
    )
    (net (code "169") (name "unconnected-(P4-IO10-Pad3)") (class "Default")
      (node (ref "P4") (pin "3") (pinfunction "IO10_3") (pintype "passive"))
    )
    (net (code "170") (name "unconnected-(P4-IO11-Pad4)") (class "Default")
      (node (ref "P4") (pin "4") (pinfunction "IO11_4") (pintype "passive"))
    )
    (net (code "171") (name "unconnected-(P4-IO12-Pad1)") (class "Default")
      (node (ref "P4") (pin "1") (pinfunction "IO12_1") (pintype "passive"))
    )
    (net (code "172") (name "unconnected-(P4-IO13-Pad2)") (class "Default")
      (node (ref "P4") (pin "2") (pinfunction "IO13_2") (pintype "passive"))
    )
    (net (code "173") (name "unconnected-(P5-GND-Pad2)") (class "Default")
      (node (ref "P5") (pin "2") (pinfunction "GND_2") (pintype "passive"))
    )
    (net (code "174") (name "unconnected-(P5-PVDD-Pad5)") (class "Default")
      (node (ref "P5") (pin "5") (pinfunction "PVDD_5") (pintype "passive"))
    )
    (net (code "175") (name "unconnected-(P13-Pad8)") (class "Default")
      (node (ref "P13") (pin "8") (pinfunction "8_8") (pintype "passive"))
    )
    (net (code "176") (name "unconnected-(U3A-PA0-WKUP-Pad23)") (class "Default")
      (node (ref "U3") (pin "23") (pinfunction "PA0-WKUP_23") (pintype "passive"))
    )
    (net (code "177") (name "unconnected-(U3A-PA3-Pad26)") (class "Default")
      (node (ref "U3") (pin "26") (pinfunction "PA3_26") (pintype "passive"))
    )
    (net (code "178") (name "unconnected-(U3A-PB10-Pad47)") (class "Default")
      (node (ref "U3") (pin "47") (pinfunction "PB10_47") (pintype "passive"))
    )
    (net (code "179") (name "unconnected-(U3A-PC3-Pad18)") (class "Default")
      (node (ref "U3") (pin "18") (pinfunction "PC3_18") (pintype "passive"))
    )
    (net (code "180") (name "unconnected-(U3A-PC5-Pad34)") (class "Default")
      (node (ref "U3") (pin "34") (pinfunction "PC5_34") (pintype "passive"))
    )
    (net (code "181") (name "unconnected-(U3A-PD2-Pad83)") (class "Default")
      (node (ref "U3") (pin "83") (pinfunction "PD2_83") (pintype "passive"))
    )
    (net (code "182") (name "unconnected-(U3A-PD3-Pad84)") (class "Default")
      (node (ref "U3") (pin "84") (pinfunction "PD3_84") (pintype "passive"))
    )
    (net (code "183") (name "unconnected-(U3A-PD4-Pad85)") (class "Default")
      (node (ref "U3") (pin "85") (pinfunction "PD4_85") (pintype "passive"))
    )
    (net (code "184") (name "unconnected-(U3A-PD7-Pad88)") (class "Default")
      (node (ref "U3") (pin "88") (pinfunction "PD7_88") (pintype "passive"))
    )
    (net (code "185") (name "unconnected-(U3A-PD11-Pad58)") (class "Default")
      (node (ref "U3") (pin "58") (pinfunction "PD11_58") (pintype "passive"))
    )
    (net (code "186") (name "unconnected-(U3A-PD12-Pad59)") (class "Default")
      (node (ref "U3") (pin "59") (pinfunction "PD12_59") (pintype "passive"))
    )
    (net (code "187") (name "unconnected-(U3A-PD13-Pad60)") (class "Default")
      (node (ref "U3") (pin "60") (pinfunction "PD13_60") (pintype "passive"))
    )
    (net (code "188") (name "unconnected-(U3A-PD14-Pad61)") (class "Default")
      (node (ref "U3") (pin "61") (pinfunction "PD14_61") (pintype "passive"))
    )
    (net (code "189") (name "unconnected-(U4-NC-Pad4)") (class "Default")
      (node (ref "U4") (pin "4") (pinfunction "NC_4") (pintype "passive"))
    )
    (net (code "190") (name "unconnected-(X3-NC-Pad2)") (class "Default")
      (node (ref "X3") (pin "2") (pinfunction "NC_2") (pintype "power_in+no_connect"))
    )
    (net (code "191") (name "unconnected-(X3-NC-Pad4)") (class "Default")
      (node (ref "X3") (pin "4") (pinfunction "NC_4") (pintype "passive+no_connect"))
    )
  )
)
